# Power.net
KiCad netlist of a schematic drawn in Altium Designer
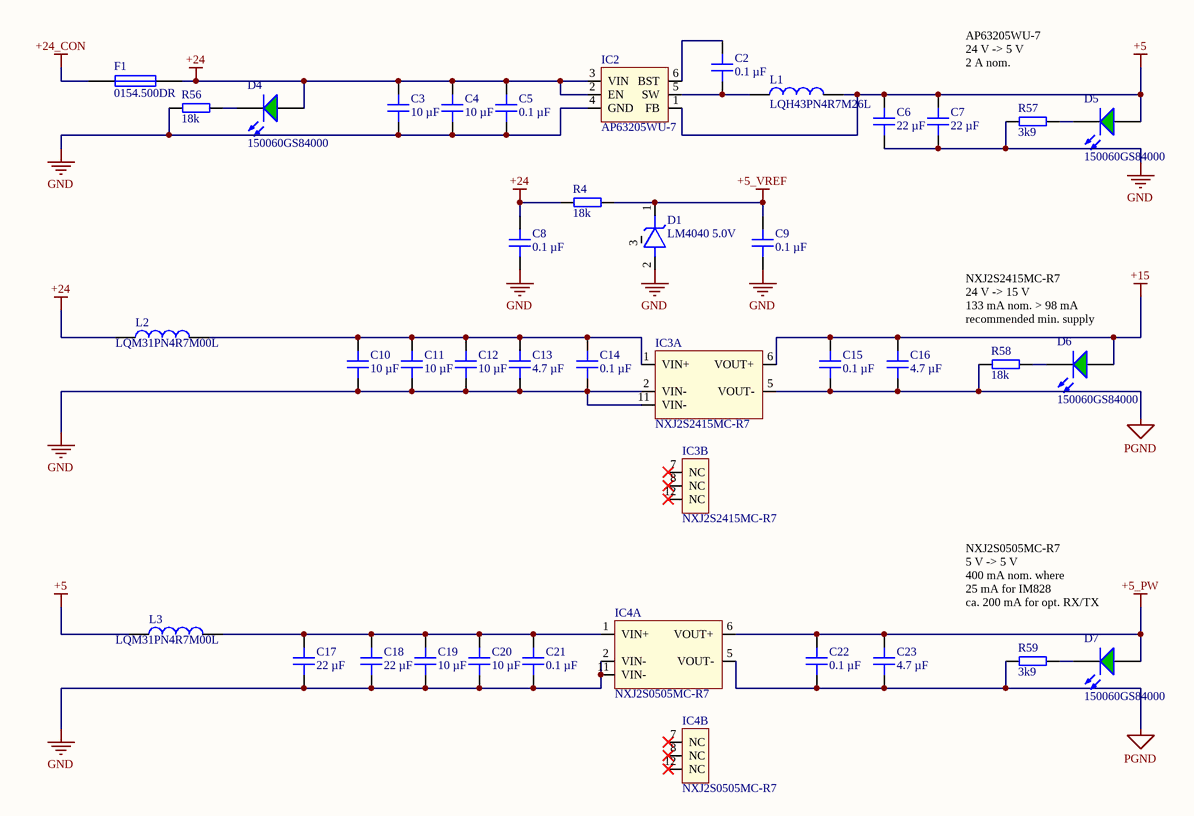
[diagram p0: Power.SchDoc]

(export (version "E")
  (design (tool "Eeschema 10.0.6"))
  (components
    (comp (ref "C2")
      (value "0.1 µF")
      (footprint "C_0603")
      (description "Capacitor 0603, 50 VDC, 0.1 µF, X7R")
      (fields
        (field (name "MANUFACTURER PART NUMBER") "C0603X104K5RAC7411")
        (field (name "MANUFACTURER") "KEMET")
        (field (name "CREATED FROM") "MGremer")
      )
      (libsource (lib "user") (part "Capacitor"))
    )
    (comp (ref "C3")
      (value "10 µF")
      (footprint "C_1206")
      (description "Capacitor 1206, 50 VDC, 10 µF, X7R")
      (fields
        (field (name "MANUFACTURER PART NUMBER") "CGA5L1X7R1H106K160AC")
        (field (name "MANUFACTURER") "TDK")
        (field (name "CREATED FROM") "MGremer")
      )
      (libsource (lib "user") (part "Capacitor"))
    )
    (comp (ref "C4")
      (value "10 µF")
      (footprint "C_1206")
      (description "Capacitor 1206, 50 VDC, 10 µF, X7R")
      (fields
        (field (name "MANUFACTURER PART NUMBER") "CGA5L1X7R1H106K160AC")
        (field (name "MANUFACTURER") "TDK")
        (field (name "CREATED FROM") "MGremer")
      )
      (libsource (lib "user") (part "Capacitor"))
    )
    (comp (ref "C5")
      (value "0.1 µF")
      (footprint "C_0603")
      (description "Capacitor 0603, 50 VDC, 0.1 µF, X7R")
      (fields
        (field (name "MANUFACTURER PART NUMBER") "C0603X104K5RAC7411")
        (field (name "MANUFACTURER") "KEMET")
        (field (name "CREATED FROM") "MGremer")
      )
      (libsource (lib "user") (part "Capacitor"))
    )
    (comp (ref "C6")
      (value "22 µF")
      (footprint "C_1206")
      (description "Capacitor 1206, 35 VDC, 22µF, X5R")
      (fields
        (field (name "MANUFACTURER PART NUMBER") "C3216X5R1V226M160AC")
        (field (name "MANUFACTURER") "TDK")
        (field (name "CREATED FROM") "VStarost")
      )
      (libsource (lib "user") (part "Capacitor"))
    )
    (comp (ref "C7")
      (value "22 µF")
      (footprint "C_1206")
      (description "Capacitor 1206, 35 VDC, 22µF, X5R")
      (fields
        (field (name "MANUFACTURER PART NUMBER") "C3216X5R1V226M160AC")
        (field (name "MANUFACTURER") "TDK")
        (field (name "CREATED FROM") "VStarost")
      )
      (libsource (lib "user") (part "Capacitor"))
    )
    (comp (ref "C8")
      (value "0.1 µF")
      (footprint "C_0603")
      (description "Capacitor 0603, 50 VDC, 0.1 µF, X7R")
      (fields
        (field (name "MANUFACTURER PART NUMBER") "C0603X104K5RAC7411")
        (field (name "MANUFACTURER") "KEMET")
        (field (name "CREATED FROM") "MGremer")
      )
      (libsource (lib "user") (part "Capacitor"))
    )
    (comp (ref "C9")
      (value "0.1 µF")
      (footprint "C_0603")
      (description "Capacitor 0603, 50 VDC, 0.1 µF, X7R")
      (fields
        (field (name "MANUFACTURER PART NUMBER") "C0603X104K5RAC7411")
        (field (name "MANUFACTURER") "KEMET")
        (field (name "CREATED FROM") "MGremer")
      )
      (libsource (lib "user") (part "Capacitor"))
    )
    (comp (ref "C10")
      (value "10 µF")
      (footprint "C_1206")
      (description "Capacitor 1206, 50 VDC, 10 µF, X7R")
      (fields
        (field (name "MANUFACTURER PART NUMBER") "CGA5L1X7R1H106K160AC")
        (field (name "MANUFACTURER") "TDK")
        (field (name "CREATED FROM") "MGremer")
      )
      (libsource (lib "user") (part "Capacitor"))
    )
    (comp (ref "C11")
      (value "10 µF")
      (footprint "C_1206")
      (description "Capacitor 1206, 50 VDC, 10 µF, X7R")
      (fields
        (field (name "MANUFACTURER PART NUMBER") "CGA5L1X7R1H106K160AC")
        (field (name "MANUFACTURER") "TDK")
        (field (name "CREATED FROM") "MGremer")
      )
      (libsource (lib "user") (part "Capacitor"))
    )
    (comp (ref "C12")
      (value "10 µF")
      (footprint "C_1206")
      (description "Capacitor 1206, 50 VDC, 10 µF, X7R")
      (fields
        (field (name "MANUFACTURER PART NUMBER") "CGA5L1X7R1H106K160AC")
        (field (name "MANUFACTURER") "TDK")
        (field (name "CREATED FROM") "MGremer")
      )
      (libsource (lib "user") (part "Capacitor"))
    )
    (comp (ref "C13")
      (value "4.7 µF")
      (footprint "C_0805")
      (description "Capacitor 0805, 50 VDC, 4.7 µF, X7R")
      (fields
        (field (name "MANUFACTURER PART NUMBER") "C2012X7R1H475K125AC")
        (field (name "MANUFACTURER") "TDK")
        (field (name "CREATED FROM") "MGremer")
      )
      (libsource (lib "user") (part "Capacitor"))
    )
    (comp (ref "C14")
      (value "0.1 µF")
      (footprint "C_0603")
      (description "Capacitor 0603, 50 VDC, 0.1 µF, X7R")
      (fields
        (field (name "MANUFACTURER PART NUMBER") "C0603X104K5RAC7411")
        (field (name "MANUFACTURER") "KEMET")
        (field (name "CREATED FROM") "MGremer")
      )
      (libsource (lib "user") (part "Capacitor"))
    )
    (comp (ref "C15")
      (value "0.1 µF")
      (footprint "C_0603")
      (description "Capacitor 0603, 50 VDC, 0.1 µF, X7R")
      (fields
        (field (name "MANUFACTURER PART NUMBER") "C0603X104K5RAC7411")
        (field (name "MANUFACTURER") "KEMET")
        (field (name "CREATED FROM") "MGremer")
      )
      (libsource (lib "user") (part "Capacitor"))
    )
    (comp (ref "C16")
      (value "4.7 µF")
      (footprint "C_0805")
      (description "Capacitor 0805, 50 VDC, 4.7 µF, X7R")
      (fields
        (field (name "MANUFACTURER PART NUMBER") "C2012X7R1H475K125AC")
        (field (name "MANUFACTURER") "TDK")
        (field (name "CREATED FROM") "MGremer")
      )
      (libsource (lib "user") (part "Capacitor"))
    )
    (comp (ref "C17")
      (value "22 µF")
      (footprint "C_1206")
      (description "Capacitor 1206, 35 VDC, 22µF, X5R")
      (fields
        (field (name "MANUFACTURER PART NUMBER") "C3216X5R1V226M160AC")
        (field (name "MANUFACTURER") "TDK")
        (field (name "CREATED FROM") "VStarost")
      )
      (libsource (lib "user") (part "Capacitor"))
    )
    (comp (ref "C18")
      (value "22 µF")
      (footprint "C_1206")
      (description "Capacitor 1206, 35 VDC, 22µF, X5R")
      (fields
        (field (name "MANUFACTURER PART NUMBER") "C3216X5R1V226M160AC")
        (field (name "MANUFACTURER") "TDK")
        (field (name "CREATED FROM") "VStarost")
      )
      (libsource (lib "user") (part "Capacitor"))
    )
    (comp (ref "C19")
      (value "10 µF")
      (footprint "C_1206")
      (description "Capacitor 1206, 50 VDC, 10 µF, X7R")
      (fields
        (field (name "MANUFACTURER PART NUMBER") "CGA5L1X7R1H106K160AC")
        (field (name "MANUFACTURER") "TDK")
        (field (name "CREATED FROM") "MGremer")
      )
      (libsource (lib "user") (part "Capacitor"))
    )
    (comp (ref "C20")
      (value "10 µF")
      (footprint "C_1206")
      (description "Capacitor 1206, 50 VDC, 10 µF, X7R")
      (fields
        (field (name "MANUFACTURER PART NUMBER") "CGA5L1X7R1H106K160AC")
        (field (name "MANUFACTURER") "TDK")
        (field (name "CREATED FROM") "MGremer")
      )
      (libsource (lib "user") (part "Capacitor"))
    )
    (comp (ref "C21")
      (value "0.1 µF")
      (footprint "C_0603")
      (description "Capacitor 0603, 50 VDC, 0.1 µF, X7R")
      (fields
        (field (name "MANUFACTURER PART NUMBER") "C0603X104K5RAC7411")
        (field (name "MANUFACTURER") "KEMET")
        (field (name "CREATED FROM") "MGremer")
      )
      (libsource (lib "user") (part "Capacitor"))
    )
    (comp (ref "C22")
      (value "0.1 µF")
      (footprint "C_0603")
      (description "Capacitor 0603, 50 VDC, 0.1 µF, X7R")
      (fields
        (field (name "MANUFACTURER PART NUMBER") "C0603X104K5RAC7411")
        (field (name "MANUFACTURER") "KEMET")
        (field (name "CREATED FROM") "MGremer")
      )
      (libsource (lib "user") (part "Capacitor"))
    )
    (comp (ref "C23")
      (value "4.7 µF")
      (footprint "C_0805")
      (description "Capacitor 0805, 50 VDC, 4.7 µF, X7R")
      (fields
        (field (name "MANUFACTURER PART NUMBER") "C2012X7R1H475K125AC")
        (field (name "MANUFACTURER") "TDK")
        (field (name "CREATED FROM") "MGremer")
      )
      (libsource (lib "user") (part "Capacitor"))
    )
    (comp (ref "D1")
      (value "LM4040 5.0V")
      (footprint "SOT-23-3")
      (description "Voltage Reference, 5.0V, ±0.5%, ±15mA")
      (fields
        (field (name "MANUFACTURER PART NUMBER") "LM4040CIM3-5.0+T")
        (field (name "MANUFACTURER") "Analog Devices")
        (field (name "CREATED FROM") "VStarost")
      )
      (libsource (lib "user") (part "Vref"))
    )
    (comp (ref "D4")
      (value "150060GS84000")
      (footprint "WL-SMCW_0603")
      (description "WL-SMCW SMD Mono-color Chip LED Waterclear Green")
      (fields (field (name "MANUFACTURER") "Wuerth Elektronik") (field (name "CREATED FROM") "MGremer"))
      (libsource (lib "user") (part "LED_Green"))
    )
    (comp (ref "D5")
      (value "150060GS84000")
      (footprint "WL-SMCW_0603")
      (description "WL-SMCW SMD Mono-color Chip LED Waterclear Green")
      (fields (field (name "MANUFACTURER") "Wuerth Elektronik") (field (name "CREATED FROM") "MGremer"))
      (libsource (lib "user") (part "LED_Green"))
    )
    (comp (ref "D6")
      (value "150060GS84000")
      (footprint "WL-SMCW_0603")
      (description "WL-SMCW SMD Mono-color Chip LED Waterclear Green")
      (fields (field (name "MANUFACTURER") "Wuerth Elektronik") (field (name "CREATED FROM") "MGremer"))
      (libsource (lib "user") (part "LED_Green"))
    )
    (comp (ref "D7")
      (value "150060GS84000")
      (footprint "WL-SMCW_0603")
      (description "WL-SMCW SMD Mono-color Chip LED Waterclear Green")
      (fields (field (name "MANUFACTURER") "Wuerth Elektronik") (field (name "CREATED FROM") "MGremer"))
      (libsource (lib "user") (part "LED_Green"))
    )
    (comp (ref "F1")
      (value "0154.500DR")
      (footprint "Littlefuse_154")
      (description "Fuse OMNI BLOK 154")
      (fields (field (name "MANUFACTURER") "Littlefuse") (field (name "CREATED FROM") "MGremer"))
      (libsource (lib "user") (part "Fuse Littelfuse 154 Fuse"))
    )
    (comp (ref "IC2")
      (value "AP63205WU-7")
      (footprint "TSOT26-6")
      (description "Switching Voltage Regulators DCDC Conv HV Buck TSOT26 T&R 3K")
      (fields (field (name "MANUFACTURER") "Diodes Incorporate") (field (name "CREATED FROM") "VStarost"))
      (libsource (lib "user") (part "AP63205"))
    )
    (comp (ref "IC3")
      (value "NXJ2S2415MC-R7")
      (footprint "DCDC")
      (description "Isolated DC/DC Converters - SMD 21.6V TO 26.4V IN 15V OUT")
      (fields (field (name "MANUFACTURER") "Murata") (field (name "CREATED FROM") "VStarost"))
      (libsource (lib "user") (part "DCDC"))
    )
    (comp (ref "IC4")
      (value "NXJ2S0505MC-R7")
      (footprint "DCDC")
      (description "Isolated DC/DC Converters - SMD 4.5V TO 5.5V IN 5V OUT")
      (fields (field (name "MANUFACTURER") "Murata") (field (name "CREATED FROM") "VStarost"))
      (libsource (lib "user") (part "DCDC"))
    )
    (comp (ref "L1")
      (value "LQH43PN4R7M26L")
      (footprint "IND")
      (description "Leistungsinduktivitäten – SMD 4.7 UH 20%")
      (fields
        (field (name "MF") "EPCOS / TDK")
        (field (name "MPN") "B82464G4154M")
        (field (name "CREATED FROM") "VStarost")
      )
      (libsource (lib "user") (part "B82464G4154M"))
    )
    (comp (ref "L2")
      (value "LQM31PN4R7M00L")
      (footprint "IND 1206_3216")
      (description "Power Inductors - SMD 4.7 UH 20%")
      (fields
        (field (name "MF") "EPCOS / TDK")
        (field (name "MPN") "B82464G4154M")
        (field (name "CREATED FROM") "VStarost")
      )
      (libsource (lib "user") (part "B82464G4154M"))
    )
    (comp (ref "L3")
      (value "LQM31PN4R7M00L")
      (footprint "IND 1206_3216")
      (description "Power Inductors - SMD 4.7 UH 20%")
      (fields
        (field (name "MF") "EPCOS / TDK")
        (field (name "MPN") "B82464G4154M")
        (field (name "CREATED FROM") "VStarost")
      )
      (libsource (lib "user") (part "B82464G4154M"))
    )
    (comp (ref "R4")
      (value "18k")
      (footprint "RES 0603_1608")
      (description "SMD resistor E24 series")
      (fields
        (field (name "MANUFACTURER PART NUMBER") "RK73B1JTTD183J")
        (field (name "MANUFACTURER") "KOA Speer")
        (field (name "CREATED FROM") "MGremer")
      )
      (libsource (lib "user") (part "Resistor"))
    )
    (comp (ref "R56")
      (value "18k")
      (footprint "RES 0603_1608")
      (description "SMD resistor E24 series")
      (fields
        (field (name "MANUFACTURER PART NUMBER") "RK73B1JTTD183J")
        (field (name "MANUFACTURER") "KOA Speer")
        (field (name "CREATED FROM") "MGremer")
      )
      (libsource (lib "user") (part "Resistor"))
    )
    (comp (ref "R57")
      (value "3k9")
      (footprint "RES 0603_1608")
      (description "SMD resistor E24 series")
      (fields
        (field (name "MANUFACTURER PART NUMBER") "RK73B1JTTDD392J")
        (field (name "MANUFACTURER") "KOA Speer")
        (field (name "CREATED FROM") "MGremer")
      )
      (libsource (lib "user") (part "Resistor"))
    )
    (comp (ref "R58")
      (value "18k")
      (footprint "RES 0603_1608")
      (description "SMD resistor E24 series")
      (fields
        (field (name "MANUFACTURER PART NUMBER") "RK73B1JTTD183J")
        (field (name "MANUFACTURER") "KOA Speer")
        (field (name "CREATED FROM") "MGremer")
      )
      (libsource (lib "user") (part "Resistor"))
    )
    (comp (ref "R59")
      (value "3k9")
      (footprint "RES 0603_1608")
      (description "SMD resistor E24 series")
      (fields
        (field (name "MANUFACTURER PART NUMBER") "RK73B1JTTDD392J")
        (field (name "MANUFACTURER") "KOA Speer")
        (field (name "CREATED FROM") "MGremer")
      )
      (libsource (lib "user") (part "Resistor"))
    )
  )
  (nets
    (net (code "1") (name "+5") (class "Default")
      (node (ref "C6") (pin "2") (pinfunction "2_2") (pintype "passive"))
      (node (ref "C7") (pin "2") (pinfunction "2_2") (pintype "passive"))
      (node (ref "D5") (pin "2") (pinfunction "A_2") (pintype "passive"))
      (node (ref "IC2") (pin "1") (pinfunction "FB_1") (pintype "passive"))
      (node (ref "L1") (pin "2") (pinfunction "2_2") (pintype "passive"))
      (node (ref "L3") (pin "1") (pinfunction "1_1") (pintype "passive"))
    )
    (net (code "2") (name "+5_PW") (class "Default")
      (node (ref "C22") (pin "2") (pinfunction "2_2") (pintype "passive"))
      (node (ref "C23") (pin "2") (pinfunction "2_2") (pintype "passive"))
      (node (ref "D7") (pin "2") (pinfunction "A_2") (pintype "passive"))
      (node (ref "IC4") (pin "6") (pinfunction "VOUT+_6") (pintype "passive"))
    )
    (net (code "3") (name "+5_VREF") (class "Default")
      (node (ref "C9") (pin "2") (pinfunction "2_2") (pintype "passive"))
      (node (ref "D1") (pin "1") (pinfunction "K_1") (pintype "passive"))
      (node (ref "R4") (pin "2") (pinfunction "2_2") (pintype "passive"))
    )
    (net (code "4") (name "+15") (class "Default")
      (node (ref "C15") (pin "2") (pinfunction "2_2") (pintype "passive"))
      (node (ref "C16") (pin "2") (pinfunction "2_2") (pintype "passive"))
      (node (ref "D6") (pin "2") (pinfunction "A_2") (pintype "passive"))
      (node (ref "IC3") (pin "6") (pinfunction "VOUT+_6") (pintype "passive"))
    )
    (net (code "5") (name "+24") (class "Default")
      (node (ref "C3") (pin "2") (pinfunction "2_2") (pintype "passive"))
      (node (ref "C4") (pin "2") (pinfunction "2_2") (pintype "passive"))
      (node (ref "C5") (pin "2") (pinfunction "2_2") (pintype "passive"))
      (node (ref "C8") (pin "2") (pinfunction "2_2") (pintype "passive"))
      (node (ref "D4") (pin "2") (pinfunction "A_2") (pintype "passive"))
      (node (ref "F1") (pin "2") (pinfunction "2_2") (pintype "passive"))
      (node (ref "IC2") (pin "2") (pinfunction "EN_2") (pintype "passive"))
      (node (ref "IC2") (pin "3") (pinfunction "VIN_3") (pintype "passive"))
      (node (ref "L2") (pin "1") (pinfunction "1_1") (pintype "passive"))
      (node (ref "R4") (pin "1") (pinfunction "1_1") (pintype "passive"))
    )
    (net (code "6") (name "+24_CON") (class "Default")
      (node (ref "F1") (pin "1") (pinfunction "1_1") (pintype "passive"))
    )
    (net (code "7") (name "GND") (class "Default")
      (node (ref "C10") (pin "1") (pinfunction "1_1") (pintype "passive"))
      (node (ref "C11") (pin "1") (pinfunction "1_1") (pintype "passive"))
      (node (ref "C12") (pin "1") (pinfunction "1_1") (pintype "passive"))
      (node (ref "C13") (pin "1") (pinfunction "1_1") (pintype "passive"))
      (node (ref "C14") (pin "1") (pinfunction "1_1") (pintype "passive"))
      (node (ref "C17") (pin "1") (pinfunction "1_1") (pintype "passive"))
      (node (ref "C18") (pin "1") (pinfunction "1_1") (pintype "passive"))
      (node (ref "C19") (pin "1") (pinfunction "1_1") (pintype "passive"))
      (node (ref "C20") (pin "1") (pinfunction "1_1") (pintype "passive"))
      (node (ref "C21") (pin "1") (pinfunction "1_1") (pintype "passive"))
      (node (ref "C3") (pin "1") (pinfunction "1_1") (pintype "passive"))
      (node (ref "C4") (pin "1") (pinfunction "1_1") (pintype "passive"))
      (node (ref "C5") (pin "1") (pinfunction "1_1") (pintype "passive"))
      (node (ref "C6") (pin "1") (pinfunction "1_1") (pintype "passive"))
      (node (ref "C7") (pin "1") (pinfunction "1_1") (pintype "passive"))
      (node (ref "C8") (pin "1") (pinfunction "1_1") (pintype "passive"))
      (node (ref "C9") (pin "1") (pinfunction "1_1") (pintype "passive"))
      (node (ref "D1") (pin "2") (pinfunction "A_2") (pintype "passive"))
      (node (ref "IC2") (pin "4") (pinfunction "GND_4") (pintype "passive"))
      (node (ref "IC3") (pin "11") (pinfunction "VIN-_11") (pintype "passive"))
      (node (ref "IC3") (pin "2") (pinfunction "VIN-_2") (pintype "passive"))
      (node (ref "IC4") (pin "11") (pinfunction "VIN-_11") (pintype "passive"))
      (node (ref "IC4") (pin "2") (pinfunction "VIN-_2") (pintype "passive"))
      (node (ref "R56") (pin "1") (pinfunction "1_1") (pintype "passive"))
      (node (ref "R57") (pin "1") (pinfunction "1_1") (pintype "passive"))
    )
    (net (code "8") (name "Net-(D4-K)") (class "Default")
      (node (ref "D4") (pin "1") (pinfunction "K_1") (pintype "passive"))
      (node (ref "R56") (pin "2") (pinfunction "2_2") (pintype "passive"))
    )
    (net (code "9") (name "Net-(D5-K)") (class "Default")
      (node (ref "D5") (pin "1") (pinfunction "K_1") (pintype "passive"))
      (node (ref "R57") (pin "2") (pinfunction "2_2") (pintype "passive"))
    )
    (net (code "10") (name "Net-(D6-K)") (class "Default")
      (node (ref "D6") (pin "1") (pinfunction "K_1") (pintype "passive"))
      (node (ref "R58") (pin "2") (pinfunction "2_2") (pintype "passive"))
    )
    (net (code "11") (name "Net-(D7-K)") (class "Default")
      (node (ref "D7") (pin "1") (pinfunction "K_1") (pintype "passive"))
      (node (ref "R59") (pin "2") (pinfunction "2_2") (pintype "passive"))
    )
    (net (code "12") (name "Net-(IC2-BST)") (class "Default")
      (node (ref "C2") (pin "2") (pinfunction "2_2") (pintype "passive"))
      (node (ref "IC2") (pin "6") (pinfunction "BST_6") (pintype "passive"))
    )
    (net (code "13") (name "Net-(IC2-SW)") (class "Default")
      (node (ref "C2") (pin "1") (pinfunction "1_1") (pintype "passive"))
      (node (ref "IC2") (pin "5") (pinfunction "SW_5") (pintype "passive"))
      (node (ref "L1") (pin "1") (pinfunction "1_1") (pintype "passive"))
    )
    (net (code "14") (name "Net-(IC3A-VIN+)") (class "Default")
      (node (ref "C10") (pin "2") (pinfunction "2_2") (pintype "passive"))
      (node (ref "C11") (pin "2") (pinfunction "2_2") (pintype "passive"))
      (node (ref "C12") (pin "2") (pinfunction "2_2") (pintype "passive"))
      (node (ref "C13") (pin "2") (pinfunction "2_2") (pintype "passive"))
      (node (ref "C14") (pin "2") (pinfunction "2_2") (pintype "passive"))
      (node (ref "IC3") (pin "1") (pinfunction "VIN+_1") (pintype "passive"))
      (node (ref "L2") (pin "2") (pinfunction "2_2") (pintype "passive"))
    )
    (net (code "15") (name "Net-(IC4A-VIN+)") (class "Default")
      (node (ref "C17") (pin "2") (pinfunction "2_2") (pintype "passive"))
      (node (ref "C18") (pin "2") (pinfunction "2_2") (pintype "passive"))
      (node (ref "C19") (pin "2") (pinfunction "2_2") (pintype "passive"))
      (node (ref "C20") (pin "2") (pinfunction "2_2") (pintype "passive"))
      (node (ref "C21") (pin "2") (pinfunction "2_2") (pintype "passive"))
      (node (ref "IC4") (pin "1") (pinfunction "VIN+_1") (pintype "passive"))
      (node (ref "L3") (pin "2") (pinfunction "2_2") (pintype "passive"))
    )
    (net (code "16") (name "PGND") (class "Default")
      (node (ref "C15") (pin "1") (pinfunction "1_1") (pintype "passive"))
      (node (ref "C16") (pin "1") (pinfunction "1_1") (pintype "passive"))
      (node (ref "C22") (pin "1") (pinfunction "1_1") (pintype "passive"))
      (node (ref "C23") (pin "1") (pinfunction "1_1") (pintype "passive"))
      (node (ref "IC3") (pin "5") (pinfunction "VOUT-_5") (pintype "passive"))
      (node (ref "IC4") (pin "5") (pinfunction "VOUT-_5") (pintype "passive"))
      (node (ref "R58") (pin "1") (pinfunction "1_1") (pintype "passive"))
      (node (ref "R59") (pin "1") (pinfunction "1_1") (pintype "passive"))
    )
    (net (code "17") (name "unconnected-(D1-NC-Pad3)") (class "Default")
      (node (ref "D1") (pin "3") (pinfunction "NC_3") (pintype "passive"))
    )
    (net (code "18") (name "unconnected-(IC3B-NC-Pad7)") (class "Default")
      (node (ref "IC3") (pin "7") (pinfunction "NC_7") (pintype "passive+no_connect"))
    )
    (net (code "19") (name "unconnected-(IC3B-NC-Pad8)") (class "Default")
      (node (ref "IC3") (pin "8") (pinfunction "NC_8") (pintype "passive+no_connect"))
    )
    (net (code "20") (name "unconnected-(IC3B-NC-Pad12)") (class "Default")
      (node (ref "IC3") (pin "12") (pinfunction "NC_12") (pintype "passive+no_connect"))
    )
    (net (code "21") (name "unconnected-(IC4B-NC-Pad7)") (class "Default")
      (node (ref "IC4") (pin "7") (pinfunction "NC_7") (pintype "passive+no_connect"))
    )
    (net (code "22") (name "unconnected-(IC4B-NC-Pad8)") (class "Default")
      (node (ref "IC4") (pin "8") (pinfunction "NC_8") (pintype "passive+no_connect"))
    )
    (net (code "23") (name "unconnected-(IC4B-NC-Pad12)") (class "Default")
      (node (ref "IC4") (pin "12") (pinfunction "NC_12") (pintype "passive+no_connect"))
    )
  )
)
